# stepper_driver.net
KiCad netlist of a schematic drawn in EAGLE
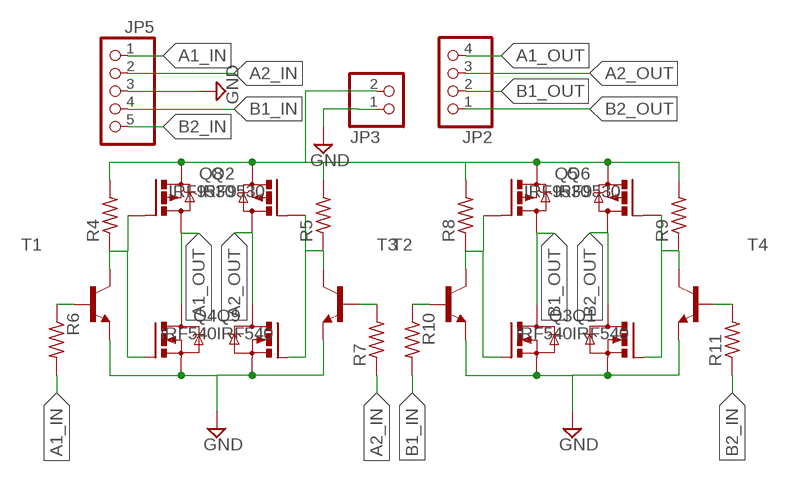
[diagram p0: schematic, sheet 1]

(export (version "E")
  (design (tool "Eeschema 10.0.6"))
  (components
    (comp (ref "JP2")
      (value "PINHD-1X4/90")
      (footprint "eagle-import:1X04_90")
      (fields (field (name "SPICEPREFIX") "E"))
      (libsource (lib "eagle-import") (part "PINHD-1X4/90"))
    )
    (comp (ref "JP3")
      (value "PINHD-1X2/90")
      (footprint "eagle-import:1X02_90")
      (libsource (lib "eagle-import") (part "PINHD-1X2/90"))
    )
    (comp (ref "JP5")
      (value "PINHD-1X5/90")
      (footprint "eagle-import:1X05_90")
      (libsource (lib "eagle-import") (part "PINHD-1X5/90"))
    )
    (comp (ref "Q1")
      (value "IRF540")
      (footprint "eagle-import:TO220BV")
      (libsource (lib "eagle-import") (part "IRF540"))
    )
    (comp (ref "Q2")
      (value "IRF9530")
      (footprint "eagle-import:TO220BV")
      (libsource (lib "eagle-import") (part "IRF9530"))
    )
    (comp (ref "Q3")
      (value "IRF540")
      (footprint "eagle-import:TO220BV")
      (libsource (lib "eagle-import") (part "IRF540"))
    )
    (comp (ref "Q4")
      (value "IRF540")
      (footprint "eagle-import:TO220BV")
      (libsource (lib "eagle-import") (part "IRF540"))
    )
    (comp (ref "Q5")
      (value "IRF9530")
      (footprint "eagle-import:TO220BV")
      (libsource (lib "eagle-import") (part "IRF9530"))
    )
    (comp (ref "Q6")
      (value "IRF9530")
      (footprint "eagle-import:TO220BV")
      (libsource (lib "eagle-import") (part "IRF9530"))
    )
    (comp (ref "Q8")
      (value "IRF9530")
      (footprint "eagle-import:TO220BV")
      (libsource (lib "eagle-import") (part "IRF9530"))
    )
    (comp (ref "Q9")
      (value "IRF540")
      (footprint "eagle-import:TO220BV")
      (libsource (lib "eagle-import") (part "IRF540"))
    )
    (comp (ref "R4")
      (value "R-US_0309/10")
      (footprint "eagle-import:0309_10")
      (libsource (lib "eagle-import") (part "R-US_0309/10"))
    )
    (comp (ref "R5")
      (value "R-US_0309/10")
      (footprint "eagle-import:0309_10")
      (libsource (lib "eagle-import") (part "R-US_0309/10"))
    )
    (comp (ref "R6")
      (value "R-US_0309/10")
      (footprint "eagle-import:0309_10")
      (libsource (lib "eagle-import") (part "R-US_0309/10"))
    )
    (comp (ref "R7")
      (value "R-US_0309/10")
      (footprint "eagle-import:0309_10")
      (libsource (lib "eagle-import") (part "R-US_0309/10"))
    )
    (comp (ref "R8")
      (value "R-US_0309/10")
      (footprint "eagle-import:0309_10")
      (libsource (lib "eagle-import") (part "R-US_0309/10"))
    )
    (comp (ref "R9")
      (value "R-US_0309/10")
      (footprint "eagle-import:0309_10")
      (libsource (lib "eagle-import") (part "R-US_0309/10"))
    )
    (comp (ref "R10")
      (value "R-US_0309/10")
      (footprint "eagle-import:0309_10")
      (libsource (lib "eagle-import") (part "R-US_0309/10"))
    )
    (comp (ref "R11")
      (value "R-US_0309/10")
      (footprint "eagle-import:0309_10")
      (libsource (lib "eagle-import") (part "R-US_0309/10"))
    )
    (comp (ref "T1")
      (value "2N2222-NPN-TO92-EBC")
      (footprint "eagle-import:TO92-EBC")
      (libsource (lib "eagle-import") (part "-NPN-TO92-EBC2N2222"))
    )
    (comp (ref "T2")
      (value "2N2222-NPN-TO92-EBC")
      (footprint "eagle-import:TO92-EBC")
      (libsource (lib "eagle-import") (part "-NPN-TO92-EBC2N2222"))
    )
    (comp (ref "T3")
      (value "2N2222-NPN-TO92-EBC")
      (footprint "eagle-import:TO92-EBC")
      (libsource (lib "eagle-import") (part "-NPN-TO92-EBC2N2222"))
    )
    (comp (ref "T4")
      (value "2N2222-NPN-TO92-EBC")
      (footprint "eagle-import:TO92-EBC")
      (libsource (lib "eagle-import") (part "-NPN-TO92-EBC2N2222"))
    )
  )
  (nets
    (net (code "1") (name "A1_IN") (class "Default")
      (node (ref "JP5") (pin "1") (pinfunction "1_1") (pintype "passive"))
      (node (ref "R6") (pin "2") (pinfunction "2_2") (pintype "passive"))
    )
    (net (code "2") (name "A1_OUT") (class "Default")
      (node (ref "JP2") (pin "4") (pinfunction "4_4") (pintype "passive"))
      (node (ref "Q8") (pin "D") (pinfunction "D_D") (pintype "passive"))
      (node (ref "Q9") (pin "D") (pinfunction "D_D") (pintype "passive"))
    )
    (net (code "3") (name "A2_IN") (class "Default")
      (node (ref "JP5") (pin "2") (pinfunction "2_2") (pintype "passive"))
      (node (ref "R7") (pin "1") (pinfunction "1_1") (pintype "passive"))
    )
    (net (code "4") (name "A2_OUT") (class "Default")
      (node (ref "JP2") (pin "3") (pinfunction "3_3") (pintype "passive"))
      (node (ref "Q2") (pin "D") (pinfunction "D_D") (pintype "passive"))
      (node (ref "Q4") (pin "D") (pinfunction "D_D") (pintype "passive"))
    )
    (net (code "5") (name "B1_IN") (class "Default")
      (node (ref "JP5") (pin "4") (pinfunction "4_4") (pintype "passive"))
      (node (ref "R10") (pin "2") (pinfunction "2_2") (pintype "passive"))
    )
    (net (code "6") (name "B1_OUT") (class "Default")
      (node (ref "JP2") (pin "2") (pinfunction "2_2") (pintype "passive"))
      (node (ref "Q1") (pin "D") (pinfunction "D_D") (pintype "passive"))
      (node (ref "Q5") (pin "D") (pinfunction "D_D") (pintype "passive"))
    )
    (net (code "7") (name "B2_IN") (class "Default")
      (node (ref "JP5") (pin "5") (pinfunction "5_5") (pintype "passive"))
      (node (ref "R11") (pin "1") (pinfunction "1_1") (pintype "passive"))
    )
    (net (code "8") (name "B2_OUT") (class "Default")
      (node (ref "JP2") (pin "1") (pinfunction "1_1") (pintype "passive"))
      (node (ref "Q3") (pin "D") (pinfunction "D_D") (pintype "passive"))
      (node (ref "Q6") (pin "D") (pinfunction "D_D") (pintype "passive"))
    )
    (net (code "9") (name "GND") (class "Default")
      (node (ref "JP3") (pin "1") (pinfunction "1_1") (pintype "passive"))
      (node (ref "JP5") (pin "3") (pinfunction "3_3") (pintype "passive"))
      (node (ref "Q1") (pin "S") (pinfunction "S_S") (pintype "passive"))
      (node (ref "Q3") (pin "S") (pinfunction "S_S") (pintype "passive"))
      (node (ref "Q4") (pin "S") (pinfunction "S_S") (pintype "passive"))
      (node (ref "Q9") (pin "S") (pinfunction "S_S") (pintype "passive"))
      (node (ref "T1") (pin "E") (pinfunction "E_E") (pintype "passive"))
      (node (ref "T2") (pin "E") (pinfunction "E_E") (pintype "passive"))
      (node (ref "T3") (pin "E") (pinfunction "E_E") (pintype "passive"))
      (node (ref "T4") (pin "E") (pinfunction "E_E") (pintype "passive"))
    )
    (net (code "10") (name "Net-(JP3-Pad2)") (class "Default")
      (node (ref "JP3") (pin "2") (pinfunction "2_2") (pintype "passive"))
      (node (ref "Q2") (pin "S") (pinfunction "S_S") (pintype "passive"))
      (node (ref "Q5") (pin "S") (pinfunction "S_S") (pintype "passive"))
      (node (ref "Q6") (pin "S") (pinfunction "S_S") (pintype "passive"))
      (node (ref "Q8") (pin "S") (pinfunction "S_S") (pintype "passive"))
      (node (ref "R4") (pin "2") (pinfunction "2_2") (pintype "passive"))
      (node (ref "R5") (pin "2") (pinfunction "2_2") (pintype "passive"))
      (node (ref "R8") (pin "2") (pinfunction "2_2") (pintype "passive"))
      (node (ref "R9") (pin "2") (pinfunction "2_2") (pintype "passive"))
    )
    (net (code "11") (name "Net-(Q1-PadG)") (class "Default")
      (node (ref "Q1") (pin "G") (pinfunction "G_G") (pintype "passive"))
      (node (ref "Q5") (pin "G") (pinfunction "G_G") (pintype "passive"))
      (node (ref "R8") (pin "1") (pinfunction "1_1") (pintype "passive"))
      (node (ref "T3") (pin "C") (pinfunction "C_C") (pintype "passive"))
    )
    (net (code "12") (name "Net-(Q2-PadG)") (class "Default")
      (node (ref "Q2") (pin "G") (pinfunction "G_G") (pintype "passive"))
      (node (ref "Q4") (pin "G") (pinfunction "G_G") (pintype "passive"))
      (node (ref "R5") (pin "1") (pinfunction "1_1") (pintype "passive"))
      (node (ref "T2") (pin "C") (pinfunction "C_C") (pintype "passive"))
    )
    (net (code "13") (name "Net-(Q3-PadG)") (class "Default")
      (node (ref "Q3") (pin "G") (pinfunction "G_G") (pintype "passive"))
      (node (ref "Q6") (pin "G") (pinfunction "G_G") (pintype "passive"))
      (node (ref "R9") (pin "1") (pinfunction "1_1") (pintype "passive"))
      (node (ref "T4") (pin "C") (pinfunction "C_C") (pintype "passive"))
    )
    (net (code "14") (name "Net-(Q8-PadG)") (class "Default")
      (node (ref "Q8") (pin "G") (pinfunction "G_G") (pintype "passive"))
      (node (ref "Q9") (pin "G") (pinfunction "G_G") (pintype "passive"))
      (node (ref "R4") (pin "1") (pinfunction "1_1") (pintype "passive"))
      (node (ref "T1") (pin "C") (pinfunction "C_C") (pintype "passive"))
    )
    (net (code "15") (name "Net-(R6-Pad1)") (class "Default")
      (node (ref "R6") (pin "1") (pinfunction "1_1") (pintype "passive"))
      (node (ref "T1") (pin "B") (pinfunction "B_B") (pintype "passive"))
    )
    (net (code "16") (name "Net-(R7-Pad2)") (class "Default")
      (node (ref "R7") (pin "2") (pinfunction "2_2") (pintype "passive"))
      (node (ref "T2") (pin "B") (pinfunction "B_B") (pintype "passive"))
    )
    (net (code "17") (name "Net-(R10-Pad1)") (class "Default")
      (node (ref "R10") (pin "1") (pinfunction "1_1") (pintype "passive"))
      (node (ref "T3") (pin "B") (pinfunction "B_B") (pintype "passive"))
    )
    (net (code "18") (name "Net-(R11-Pad2)") (class "Default")
      (node (ref "R11") (pin "2") (pinfunction "2_2") (pintype "passive"))
      (node (ref "T4") (pin "B") (pinfunction "B_B") (pintype "passive"))
    )
  )
)
